# 1Sens_lowPass.net
KiCad netlist of a schematic drawn in EAGLE
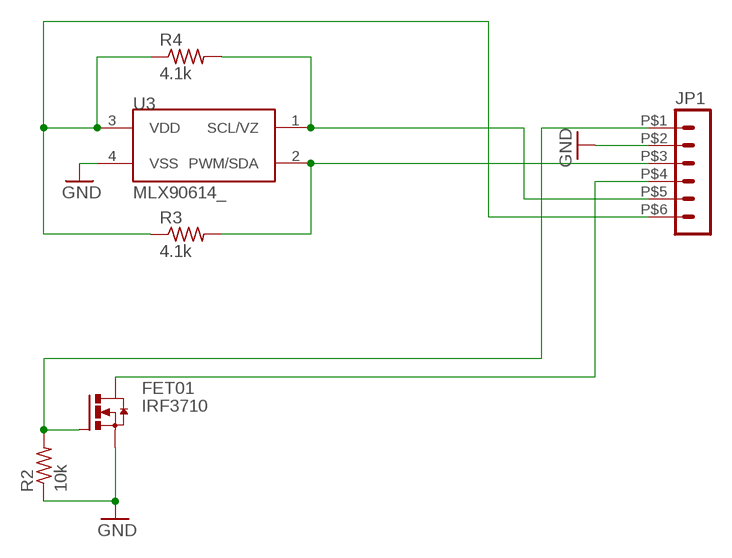
[diagram p0: schematic, sheet 1]

(export (version "E")
  (design (tool "Eeschema 10.0.6"))
  (components
    (comp (ref "FET01")
      (value "IRF3710")
      (footprint "eagle-import:TO220AH")
      (libsource (lib "eagle-import") (part "IRF3704"))
    )
    (comp (ref "JP1")
      (value "HEADER_POS6_43045-0600")
      (footprint "eagle-import:43045-0600")
      (libsource (lib "eagle-import") (part "HEADER_POS6_?43045-0600"))
    )
    (comp (ref "R2")
      (value "10k")
      (footprint "eagle-import:0207_7")
      (libsource (lib "eagle-import") (part "R-US_0207/7"))
    )
    (comp (ref "R3")
      (value "4.1k")
      (footprint "eagle-import:0204_5")
      (libsource (lib "eagle-import") (part "R-US_0204/5"))
    )
    (comp (ref "R4")
      (value "4.1k")
      (footprint "eagle-import:0204_5")
      (libsource (lib "eagle-import") (part "R-US_0204/5"))
    )
    (comp (ref "U3")
      (value "MLX90614_")
      (footprint "eagle-import:TO-39")
      (libsource (lib "eagle-import") (part "MLX90614_"))
    )
  )
  (nets
    (net (code "1") (name "GND") (class "Default")
      (node (ref "FET01") (pin "E") (pinfunction "S_E") (pintype "passive"))
      (node (ref "JP1") (pin "P$2") (pinfunction "2_P$2") (pintype "passive"))
      (node (ref "R2") (pin "1") (pinfunction "1_1") (pintype "passive"))
      (node (ref "U3") (pin "4") (pinfunction "VSS_4") (pintype "bidirectional"))
    )
    (net (code "2") (name "Net-(FET01-D)") (class "Default")
      (node (ref "FET01") (pin "C") (pinfunction "D_C") (pintype "passive"))
      (node (ref "JP1") (pin "P$4") (pinfunction "4_P$4") (pintype "passive"))
    )
    (net (code "3") (name "Net-(FET01-G)") (class "Default")
      (node (ref "FET01") (pin "B") (pinfunction "G_B") (pintype "passive"))
      (node (ref "JP1") (pin "P$1") (pinfunction "1_P$1") (pintype "passive"))
      (node (ref "R2") (pin "2") (pinfunction "2_2") (pintype "passive"))
    )
    (net (code "4") (name "Net-(JP1-3)") (class "Default")
      (node (ref "JP1") (pin "P$3") (pinfunction "3_P$3") (pintype "passive"))
      (node (ref "R3") (pin "2") (pinfunction "2_2") (pintype "passive"))
      (node (ref "U3") (pin "2") (pinfunction "PWM/SDA_2") (pintype "bidirectional"))
    )
    (net (code "5") (name "Net-(JP1-5)") (class "Default")
      (node (ref "JP1") (pin "P$5") (pinfunction "5_P$5") (pintype "passive"))
      (node (ref "R4") (pin "2") (pinfunction "2_2") (pintype "passive"))
      (node (ref "U3") (pin "1") (pinfunction "SCL/VZ_1") (pintype "bidirectional"))
    )
    (net (code "6") (name "Net-(JP1-6)") (class "Default")
      (node (ref "JP1") (pin "P$6") (pinfunction "6_P$6") (pintype "passive"))
      (node (ref "R3") (pin "1") (pinfunction "1_1") (pintype "passive"))
      (node (ref "R4") (pin "1") (pinfunction "1_1") (pintype "passive"))
      (node (ref "U3") (pin "3") (pinfunction "VDD_3") (pintype "bidirectional"))
    )
  )
)
